# LED.net
KiCad netlist of a schematic drawn in Altium Designer
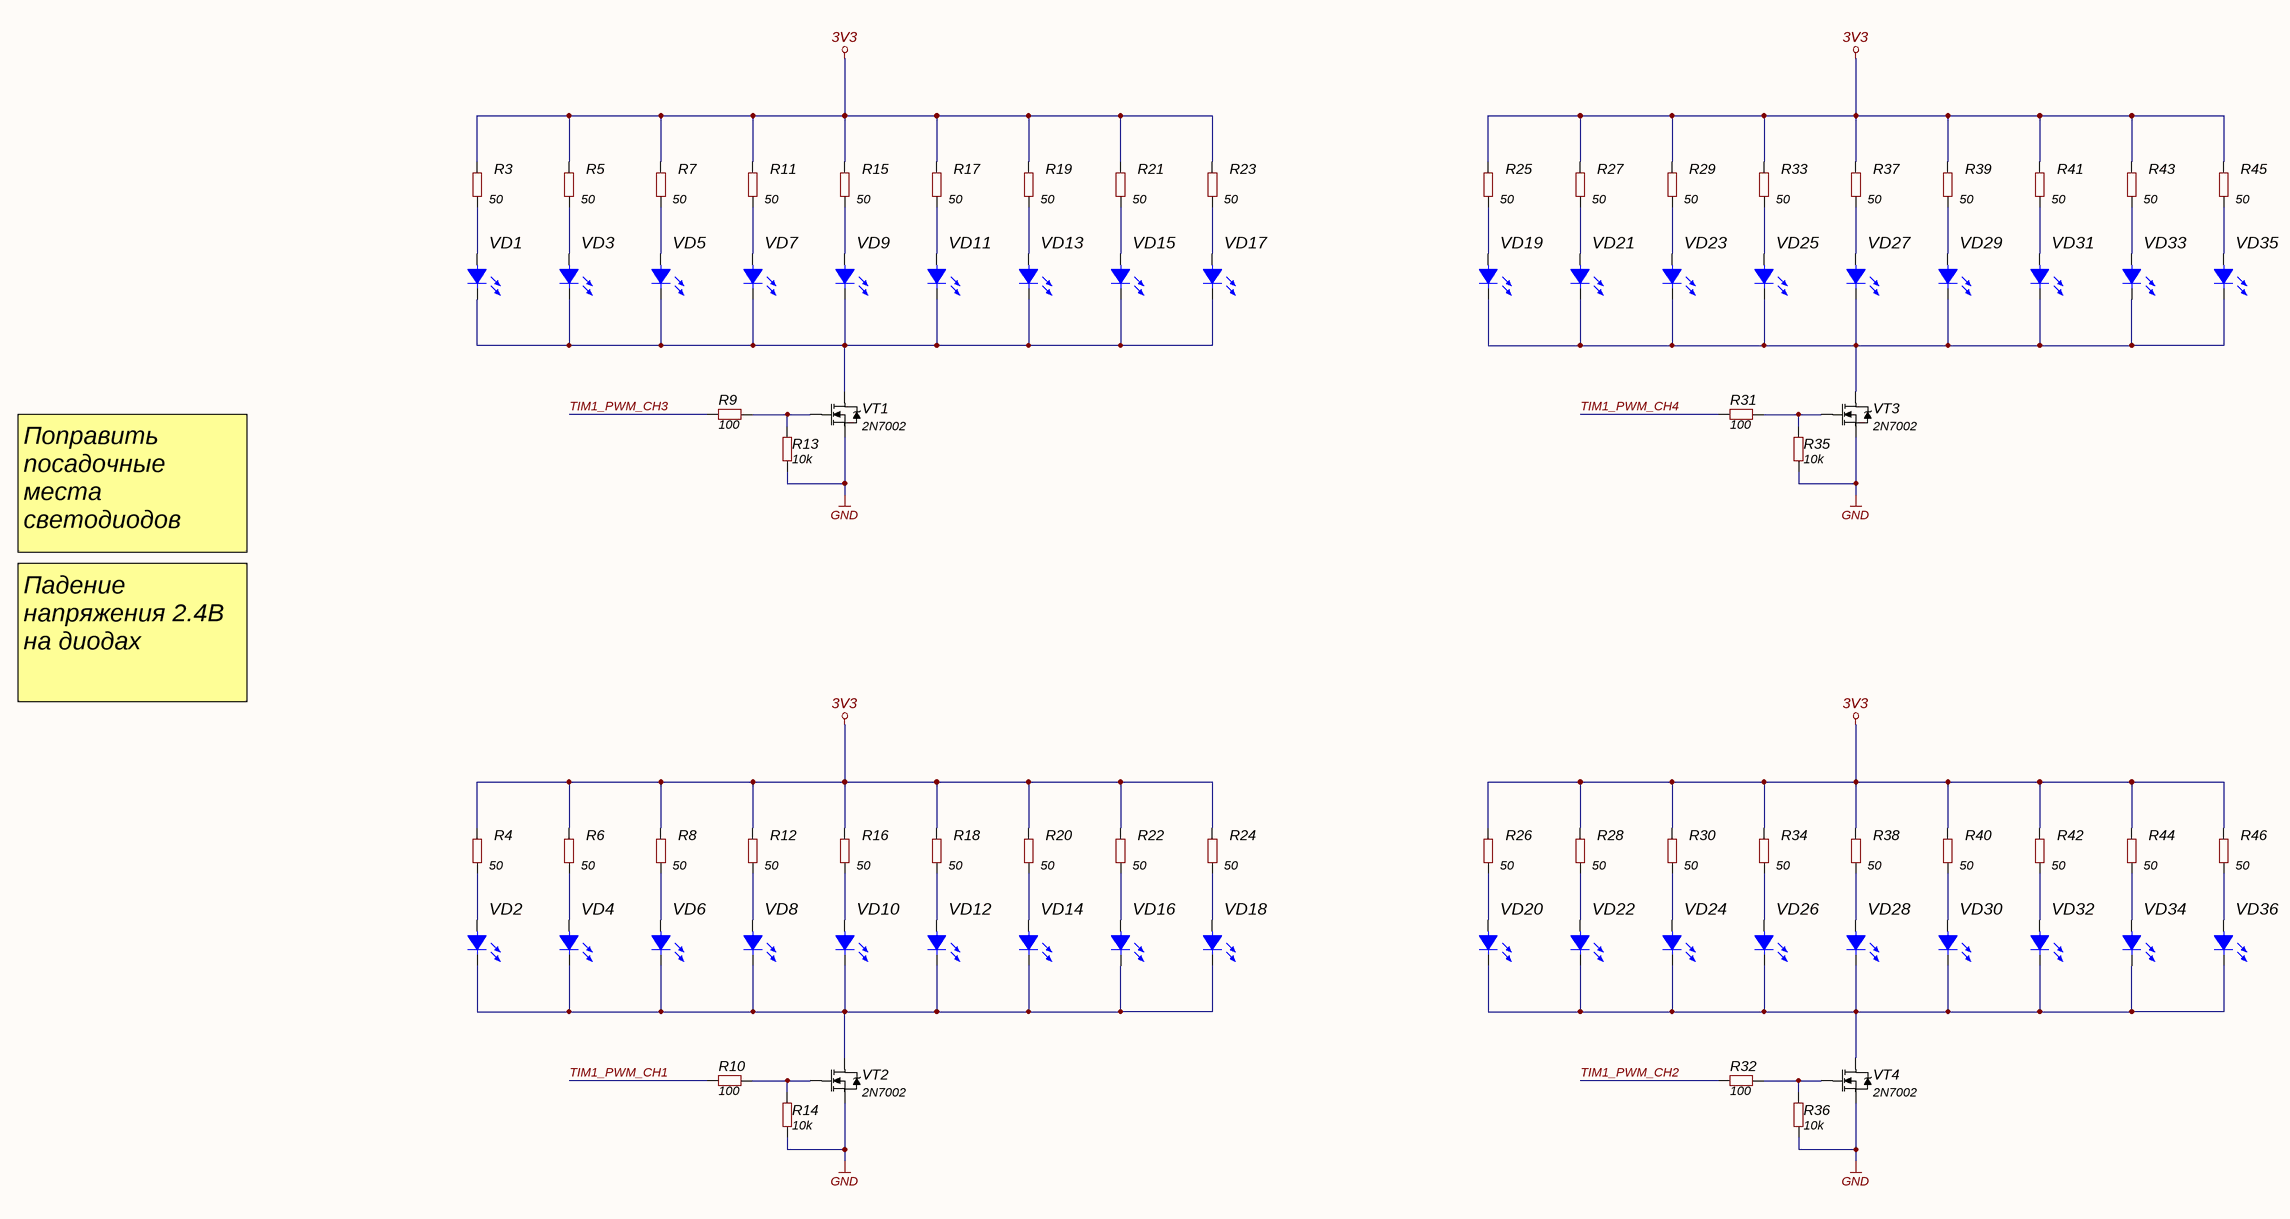
[diagram p0: LED.SchDoc]

(export (version "E")
  (design (tool "Eeschema 10.0.6"))
  (components
    (comp (ref "R3")
      (value "50")
      (footprint "RES: 0603")
      (fields
        (field (name "MANUFACTURER") "Yageo")
        (field (name "PARTNUMBER") "RC0603JR-07100RL")
        (field (name "VALUEMANUFACTURERPARTNUMBER") "Resistor film, 50, , 0603, 0.1W, -55...+125°C")
      )
      (libsource (lib "resistor") (part "Resistor_0603"))
    )
    (comp (ref "R4")
      (value "50")
      (footprint "RES: 0603")
      (fields
        (field (name "MANUFACTURER") "Yageo")
        (field (name "PARTNUMBER") "RC0603JR-07100RL")
        (field (name "VALUEMANUFACTURERPARTNUMBER") "Resistor film, 50, , 0603, 0.1W, -55...+125°C")
      )
      (libsource (lib "resistor") (part "Resistor_0603"))
    )
    (comp (ref "R5")
      (value "50")
      (footprint "RES: 0603")
      (fields
        (field (name "MANUFACTURER") "Yageo")
        (field (name "PARTNUMBER") "RC0603JR-07100RL")
        (field (name "VALUEMANUFACTURERPARTNUMBER") "Resistor film, 50, , 0603, 0.1W, -55...+125°C")
      )
      (libsource (lib "resistor") (part "Resistor_0603"))
    )
    (comp (ref "R6")
      (value "50")
      (footprint "RES: 0603")
      (fields
        (field (name "MANUFACTURER") "Yageo")
        (field (name "PARTNUMBER") "RC0603JR-07100RL")
        (field (name "VALUEMANUFACTURERPARTNUMBER") "Resistor film, 50, , 0603, 0.1W, -55...+125°C")
      )
      (libsource (lib "resistor") (part "Resistor_0603"))
    )
    (comp (ref "R7")
      (value "50")
      (footprint "RES: 0603")
      (fields
        (field (name "MANUFACTURER") "Yageo")
        (field (name "PARTNUMBER") "RC0603JR-07100RL")
        (field (name "VALUEMANUFACTURERPARTNUMBER") "Resistor film, 50, , 0603, 0.1W, -55...+125°C")
      )
      (libsource (lib "resistor") (part "Resistor_0603"))
    )
    (comp (ref "R8")
      (value "50")
      (footprint "RES: 0603")
      (fields
        (field (name "MANUFACTURER") "Yageo")
        (field (name "PARTNUMBER") "RC0603JR-07100RL")
        (field (name "VALUEMANUFACTURERPARTNUMBER") "Resistor film, 50, , 0603, 0.1W, -55...+125°C")
      )
      (libsource (lib "resistor") (part "Resistor_0603"))
    )
    (comp (ref "R9")
      (value "100")
      (footprint "RES: 0603")
      (fields
        (field (name "MANUFACTURER") "Yageo")
        (field (name "PARTNUMBER") "RC0603JR-07100RL")
        (field (name "VALUEMANUFACTURERPARTNUMBER") "Resistor film, 100, , 0603, 0.1W, -55...+125°C")
      )
      (libsource (lib "") (part "Resistor_0603_1"))
    )
    (comp (ref "R10")
      (value "100")
      (footprint "RES: 0603")
      (fields
        (field (name "MANUFACTURER") "Yageo")
        (field (name "PARTNUMBER") "RC0603JR-07100RL")
        (field (name "VALUEMANUFACTURERPARTNUMBER") "Resistor film, 100, , 0603, 0.1W, -55...+125°C")
      )
      (libsource (lib "") (part "Resistor_0603_1"))
    )
    (comp (ref "R11")
      (value "50")
      (footprint "RES: 0603")
      (fields
        (field (name "MANUFACTURER") "Yageo")
        (field (name "PARTNUMBER") "RC0603JR-07100RL")
        (field (name "VALUEMANUFACTURERPARTNUMBER") "Resistor film, 50, , 0603, 0.1W, -55...+125°C")
      )
      (libsource (lib "resistor") (part "Resistor_0603"))
    )
    (comp (ref "R12")
      (value "50")
      (footprint "RES: 0603")
      (fields
        (field (name "MANUFACTURER") "Yageo")
        (field (name "PARTNUMBER") "RC0603JR-07100RL")
        (field (name "VALUEMANUFACTURERPARTNUMBER") "Resistor film, 50, , 0603, 0.1W, -55...+125°C")
      )
      (libsource (lib "resistor") (part "Resistor_0603"))
    )
    (comp (ref "R13")
      (value "10k")
      (footprint "RES: 0603")
      (fields
        (field (name "MANUFACTURER") "Yageo")
        (field (name "PARTNUMBER") "RC0603JR-07100RL")
        (field (name "VALUEMANUFACTURERPARTNUMBER") "Resistor film, 10k, , 0603, 0.1W, -55...+125°C")
      )
      (libsource (lib "resistor") (part "Resistor_0603"))
    )
    (comp (ref "R14")
      (value "10k")
      (footprint "RES: 0603")
      (fields
        (field (name "MANUFACTURER") "Yageo")
        (field (name "PARTNUMBER") "RC0603JR-07100RL")
        (field (name "VALUEMANUFACTURERPARTNUMBER") "Resistor film, 10k, , 0603, 0.1W, -55...+125°C")
      )
      (libsource (lib "resistor") (part "Resistor_0603"))
    )
    (comp (ref "R15")
      (value "50")
      (footprint "RES: 0603")
      (fields
        (field (name "MANUFACTURER") "Yageo")
        (field (name "PARTNUMBER") "RC0603JR-07100RL")
        (field (name "VALUEMANUFACTURERPARTNUMBER") "Resistor film, 50, , 0603, 0.1W, -55...+125°C")
      )
      (libsource (lib "resistor") (part "Resistor_0603"))
    )
    (comp (ref "R16")
      (value "50")
      (footprint "RES: 0603")
      (fields
        (field (name "MANUFACTURER") "Yageo")
        (field (name "PARTNUMBER") "RC0603JR-07100RL")
        (field (name "VALUEMANUFACTURERPARTNUMBER") "Resistor film, 50, , 0603, 0.1W, -55...+125°C")
      )
      (libsource (lib "resistor") (part "Resistor_0603"))
    )
    (comp (ref "R17")
      (value "50")
      (footprint "RES: 0603")
      (fields
        (field (name "MANUFACTURER") "Yageo")
        (field (name "PARTNUMBER") "RC0603JR-07100RL")
        (field (name "VALUEMANUFACTURERPARTNUMBER") "Resistor film, 50, , 0603, 0.1W, -55...+125°C")
      )
      (libsource (lib "resistor") (part "Resistor_0603"))
    )
    (comp (ref "R18")
      (value "50")
      (footprint "RES: 0603")
      (fields
        (field (name "MANUFACTURER") "Yageo")
        (field (name "PARTNUMBER") "RC0603JR-07100RL")
        (field (name "VALUEMANUFACTURERPARTNUMBER") "Resistor film, 50, , 0603, 0.1W, -55...+125°C")
      )
      (libsource (lib "resistor") (part "Resistor_0603"))
    )
    (comp (ref "R19")
      (value "50")
      (footprint "RES: 0603")
      (fields
        (field (name "MANUFACTURER") "Yageo")
        (field (name "PARTNUMBER") "RC0603JR-07100RL")
        (field (name "VALUEMANUFACTURERPARTNUMBER") "Resistor film, 50, , 0603, 0.1W, -55...+125°C")
      )
      (libsource (lib "resistor") (part "Resistor_0603"))
    )
    (comp (ref "R20")
      (value "50")
      (footprint "RES: 0603")
      (fields
        (field (name "MANUFACTURER") "Yageo")
        (field (name "PARTNUMBER") "RC0603JR-07100RL")
        (field (name "VALUEMANUFACTURERPARTNUMBER") "Resistor film, 50, , 0603, 0.1W, -55...+125°C")
      )
      (libsource (lib "resistor") (part "Resistor_0603"))
    )
    (comp (ref "R21")
      (value "50")
      (footprint "RES: 0603")
      (fields
        (field (name "MANUFACTURER") "Yageo")
        (field (name "PARTNUMBER") "RC0603JR-07100RL")
        (field (name "VALUEMANUFACTURERPARTNUMBER") "Resistor film, 50, , 0603, 0.1W, -55...+125°C")
      )
      (libsource (lib "resistor") (part "Resistor_0603"))
    )
    (comp (ref "R22")
      (value "50")
      (footprint "RES: 0603")
      (fields
        (field (name "MANUFACTURER") "Yageo")
        (field (name "PARTNUMBER") "RC0603JR-07100RL")
        (field (name "VALUEMANUFACTURERPARTNUMBER") "Resistor film, 50, , 0603, 0.1W, -55...+125°C")
      )
      (libsource (lib "resistor") (part "Resistor_0603"))
    )
    (comp (ref "R23")
      (value "50")
      (footprint "RES: 0603")
      (fields
        (field (name "MANUFACTURER") "Yageo")
        (field (name "PARTNUMBER") "RC0603JR-07100RL")
        (field (name "VALUEMANUFACTURERPARTNUMBER") "Resistor film, 50, , 0603, 0.1W, -55...+125°C")
      )
      (libsource (lib "resistor") (part "Resistor_0603"))
    )
    (comp (ref "R24")
      (value "50")
      (footprint "RES: 0603")
      (fields
        (field (name "MANUFACTURER") "Yageo")
        (field (name "PARTNUMBER") "RC0603JR-07100RL")
        (field (name "VALUEMANUFACTURERPARTNUMBER") "Resistor film, 50, , 0603, 0.1W, -55...+125°C")
      )
      (libsource (lib "resistor") (part "Resistor_0603"))
    )
    (comp (ref "R25")
      (value "50")
      (footprint "RES: 0603")
      (fields
        (field (name "MANUFACTURER") "Yageo")
        (field (name "PARTNUMBER") "RC0603JR-07100RL")
        (field (name "VALUEMANUFACTURERPARTNUMBER") "Resistor film, 50, , 0603, 0.1W, -55...+125°C")
      )
      (libsource (lib "resistor") (part "Resistor_0603"))
    )
    (comp (ref "R26")
      (value "50")
      (footprint "RES: 0603")
      (fields
        (field (name "MANUFACTURER") "Yageo")
        (field (name "PARTNUMBER") "RC0603JR-07100RL")
        (field (name "VALUEMANUFACTURERPARTNUMBER") "Resistor film, 50, , 0603, 0.1W, -55...+125°C")
      )
      (libsource (lib "resistor") (part "Resistor_0603"))
    )
    (comp (ref "R27")
      (value "50")
      (footprint "RES: 0603")
      (fields
        (field (name "MANUFACTURER") "Yageo")
        (field (name "PARTNUMBER") "RC0603JR-07100RL")
        (field (name "VALUEMANUFACTURERPARTNUMBER") "Resistor film, 50, , 0603, 0.1W, -55...+125°C")
      )
      (libsource (lib "resistor") (part "Resistor_0603"))
    )
    (comp (ref "R28")
      (value "50")
      (footprint "RES: 0603")
      (fields
        (field (name "MANUFACTURER") "Yageo")
        (field (name "PARTNUMBER") "RC0603JR-07100RL")
        (field (name "VALUEMANUFACTURERPARTNUMBER") "Resistor film, 50, , 0603, 0.1W, -55...+125°C")
      )
      (libsource (lib "resistor") (part "Resistor_0603"))
    )
    (comp (ref "R29")
      (value "50")
      (footprint "RES: 0603")
      (fields
        (field (name "MANUFACTURER") "Yageo")
        (field (name "PARTNUMBER") "RC0603JR-07100RL")
        (field (name "VALUEMANUFACTURERPARTNUMBER") "Resistor film, 50, , 0603, 0.1W, -55...+125°C")
      )
      (libsource (lib "resistor") (part "Resistor_0603"))
    )
    (comp (ref "R30")
      (value "50")
      (footprint "RES: 0603")
      (fields
        (field (name "MANUFACTURER") "Yageo")
        (field (name "PARTNUMBER") "RC0603JR-07100RL")
        (field (name "VALUEMANUFACTURERPARTNUMBER") "Resistor film, 50, , 0603, 0.1W, -55...+125°C")
      )
      (libsource (lib "resistor") (part "Resistor_0603"))
    )
    (comp (ref "R31")
      (value "100")
      (footprint "RES: 0603")
      (fields
        (field (name "MANUFACTURER") "Yageo")
        (field (name "PARTNUMBER") "RC0603JR-07100RL")
        (field (name "VALUEMANUFACTURERPARTNUMBER") "Resistor film, 100, , 0603, 0.1W, -55...+125°C")
      )
      (libsource (lib "") (part "Resistor_0603_1"))
    )
    (comp (ref "R32")
      (value "100")
      (footprint "RES: 0603")
      (fields
        (field (name "MANUFACTURER") "Yageo")
        (field (name "PARTNUMBER") "RC0603JR-07100RL")
        (field (name "VALUEMANUFACTURERPARTNUMBER") "Resistor film, 100, , 0603, 0.1W, -55...+125°C")
      )
      (libsource (lib "") (part "Resistor_0603_1"))
    )
    (comp (ref "R33")
      (value "50")
      (footprint "RES: 0603")
      (fields
        (field (name "MANUFACTURER") "Yageo")
        (field (name "PARTNUMBER") "RC0603JR-07100RL")
        (field (name "VALUEMANUFACTURERPARTNUMBER") "Resistor film, 50, , 0603, 0.1W, -55...+125°C")
      )
      (libsource (lib "resistor") (part "Resistor_0603"))
    )
    (comp (ref "R34")
      (value "50")
      (footprint "RES: 0603")
      (fields
        (field (name "MANUFACTURER") "Yageo")
        (field (name "PARTNUMBER") "RC0603JR-07100RL")
        (field (name "VALUEMANUFACTURERPARTNUMBER") "Resistor film, 50, , 0603, 0.1W, -55...+125°C")
      )
      (libsource (lib "resistor") (part "Resistor_0603"))
    )
    (comp (ref "R35")
      (value "10k")
      (footprint "RES: 0603")
      (fields
        (field (name "MANUFACTURER") "Yageo")
        (field (name "PARTNUMBER") "RC0603JR-07100RL")
        (field (name "VALUEMANUFACTURERPARTNUMBER") "Resistor film, 10k, , 0603, 0.1W, -55...+125°C")
      )
      (libsource (lib "resistor") (part "Resistor_0603"))
    )
    (comp (ref "R36")
      (value "10k")
      (footprint "RES: 0603")
      (fields
        (field (name "MANUFACTURER") "Yageo")
        (field (name "PARTNUMBER") "RC0603JR-07100RL")
        (field (name "VALUEMANUFACTURERPARTNUMBER") "Resistor film, 10k, , 0603, 0.1W, -55...+125°C")
      )
      (libsource (lib "resistor") (part "Resistor_0603"))
    )
    (comp (ref "R37")
      (value "50")
      (footprint "RES: 0603")
      (fields
        (field (name "MANUFACTURER") "Yageo")
        (field (name "PARTNUMBER") "RC0603JR-07100RL")
        (field (name "VALUEMANUFACTURERPARTNUMBER") "Resistor film, 50, , 0603, 0.1W, -55...+125°C")
      )
      (libsource (lib "resistor") (part "Resistor_0603"))
    )
    (comp (ref "R38")
      (value "50")
      (footprint "RES: 0603")
      (fields
        (field (name "MANUFACTURER") "Yageo")
        (field (name "PARTNUMBER") "RC0603JR-07100RL")
        (field (name "VALUEMANUFACTURERPARTNUMBER") "Resistor film, 50, , 0603, 0.1W, -55...+125°C")
      )
      (libsource (lib "resistor") (part "Resistor_0603"))
    )
    (comp (ref "R39")
      (value "50")
      (footprint "RES: 0603")
      (fields
        (field (name "MANUFACTURER") "Yageo")
        (field (name "PARTNUMBER") "RC0603JR-07100RL")
        (field (name "VALUEMANUFACTURERPARTNUMBER") "Resistor film, 50, , 0603, 0.1W, -55...+125°C")
      )
      (libsource (lib "resistor") (part "Resistor_0603"))
    )
    (comp (ref "R40")
      (value "50")
      (footprint "RES: 0603")
      (fields
        (field (name "MANUFACTURER") "Yageo")
        (field (name "PARTNUMBER") "RC0603JR-07100RL")
        (field (name "VALUEMANUFACTURERPARTNUMBER") "Resistor film, 50, , 0603, 0.1W, -55...+125°C")
      )
      (libsource (lib "resistor") (part "Resistor_0603"))
    )
    (comp (ref "R41")
      (value "50")
      (footprint "RES: 0603")
      (fields
        (field (name "MANUFACTURER") "Yageo")
        (field (name "PARTNUMBER") "RC0603JR-07100RL")
        (field (name "VALUEMANUFACTURERPARTNUMBER") "Resistor film, 50, , 0603, 0.1W, -55...+125°C")
      )
      (libsource (lib "resistor") (part "Resistor_0603"))
    )
    (comp (ref "R42")
      (value "50")
      (footprint "RES: 0603")
      (fields
        (field (name "MANUFACTURER") "Yageo")
        (field (name "PARTNUMBER") "RC0603JR-07100RL")
        (field (name "VALUEMANUFACTURERPARTNUMBER") "Resistor film, 50, , 0603, 0.1W, -55...+125°C")
      )
      (libsource (lib "resistor") (part "Resistor_0603"))
    )
    (comp (ref "R43")
      (value "50")
      (footprint "RES: 0603")
      (fields
        (field (name "MANUFACTURER") "Yageo")
        (field (name "PARTNUMBER") "RC0603JR-07100RL")
        (field (name "VALUEMANUFACTURERPARTNUMBER") "Resistor film, 50, , 0603, 0.1W, -55...+125°C")
      )
      (libsource (lib "resistor") (part "Resistor_0603"))
    )
    (comp (ref "R44")
      (value "50")
      (footprint "RES: 0603")
      (fields
        (field (name "MANUFACTURER") "Yageo")
        (field (name "PARTNUMBER") "RC0603JR-07100RL")
        (field (name "VALUEMANUFACTURERPARTNUMBER") "Resistor film, 50, , 0603, 0.1W, -55...+125°C")
      )
      (libsource (lib "resistor") (part "Resistor_0603"))
    )
    (comp (ref "R45")
      (value "50")
      (footprint "RES: 0603")
      (fields
        (field (name "MANUFACTURER") "Yageo")
        (field (name "PARTNUMBER") "RC0603JR-07100RL")
        (field (name "VALUEMANUFACTURERPARTNUMBER") "Resistor film, 50, , 0603, 0.1W, -55...+125°C")
      )
      (libsource (lib "resistor") (part "Resistor_0603"))
    )
    (comp (ref "R46")
      (value "50")
      (footprint "RES: 0603")
      (fields
        (field (name "MANUFACTURER") "Yageo")
        (field (name "PARTNUMBER") "RC0603JR-07100RL")
        (field (name "VALUEMANUFACTURERPARTNUMBER") "Resistor film, 50, , 0603, 0.1W, -55...+125°C")
      )
      (libsource (lib "resistor") (part "Resistor_0603"))
    )
    (comp (ref "VD1")
      (value "~")
      (footprint "LED: 1206Y")
      (fields (field (name "VALUEMANUFACTURERPARTNUMBER") "LED, Green, *, *, *, -55...+150°C"))
      (libsource (lib "diode") (part "LED_single"))
    )
    (comp (ref "VD2")
      (value "~")
      (footprint "LED: 1206Y")
      (fields (field (name "VALUEMANUFACTURERPARTNUMBER") "LED, Green, *, *, *, -55...+150°C"))
      (libsource (lib "diode") (part "LED_single"))
    )
    (comp (ref "VD3")
      (value "~")
      (footprint "LED: 1206Y")
      (fields (field (name "VALUEMANUFACTURERPARTNUMBER") "LED, Green, *, *, *, -55...+150°C"))
      (libsource (lib "diode") (part "LED_single"))
    )
    (comp (ref "VD4")
      (value "~")
      (footprint "LED: 1206Y")
      (fields (field (name "VALUEMANUFACTURERPARTNUMBER") "LED, Green, *, *, *, -55...+150°C"))
      (libsource (lib "diode") (part "LED_single"))
    )
    (comp (ref "VD5")
      (value "~")
      (footprint "LED: 1206Y")
      (fields (field (name "VALUEMANUFACTURERPARTNUMBER") "LED, Green, *, *, *, -55...+150°C"))
      (libsource (lib "diode") (part "LED_single"))
    )
    (comp (ref "VD6")
      (value "~")
      (footprint "LED: 1206Y")
      (fields (field (name "VALUEMANUFACTURERPARTNUMBER") "LED, Green, *, *, *, -55...+150°C"))
      (libsource (lib "diode") (part "LED_single"))
    )
    (comp (ref "VD7")
      (value "~")
      (footprint "LED: 1206Y")
      (fields (field (name "VALUEMANUFACTURERPARTNUMBER") "LED, Green, *, *, *, -55...+150°C"))
      (libsource (lib "diode") (part "LED_single"))
    )
    (comp (ref "VD8")
      (value "~")
      (footprint "LED: 1206Y")
      (fields (field (name "VALUEMANUFACTURERPARTNUMBER") "LED, Green, *, *, *, -55...+150°C"))
      (libsource (lib "diode") (part "LED_single"))
    )
    (comp (ref "VD9")
      (value "~")
      (footprint "LED: 1206Y")
      (fields (field (name "VALUEMANUFACTURERPARTNUMBER") "LED, Green, *, *, *, -55...+150°C"))
      (libsource (lib "diode") (part "LED_single"))
    )
    (comp (ref "VD10")
      (value "~")
      (footprint "LED: 1206Y")
      (fields (field (name "VALUEMANUFACTURERPARTNUMBER") "LED, Green, *, *, *, -55...+150°C"))
      (libsource (lib "diode") (part "LED_single"))
    )
    (comp (ref "VD11")
      (value "~")
      (footprint "LED: 1206Y")
      (fields (field (name "VALUEMANUFACTURERPARTNUMBER") "LED, Green, *, *, *, -55...+150°C"))
      (libsource (lib "diode") (part "LED_single"))
    )
    (comp (ref "VD12")
      (value "~")
      (footprint "LED: 1206Y")
      (fields (field (name "VALUEMANUFACTURERPARTNUMBER") "LED, Green, *, *, *, -55...+150°C"))
      (libsource (lib "diode") (part "LED_single"))
    )
    (comp (ref "VD13")
      (value "~")
      (footprint "LED: 1206Y")
      (fields (field (name "VALUEMANUFACTURERPARTNUMBER") "LED, Green, *, *, *, -55...+150°C"))
      (libsource (lib "diode") (part "LED_single"))
    )
    (comp (ref "VD14")
      (value "~")
      (footprint "LED: 1206Y")
      (fields (field (name "VALUEMANUFACTURERPARTNUMBER") "LED, Green, *, *, *, -55...+150°C"))
      (libsource (lib "diode") (part "LED_single"))
    )
    (comp (ref "VD15")
      (value "~")
      (footprint "LED: 1206Y")
      (fields (field (name "VALUEMANUFACTURERPARTNUMBER") "LED, Green, *, *, *, -55...+150°C"))
      (libsource (lib "diode") (part "LED_single"))
    )
    (comp (ref "VD16")
      (value "~")
      (footprint "LED: 1206Y")
      (fields (field (name "VALUEMANUFACTURERPARTNUMBER") "LED, Green, *, *, *, -55...+150°C"))
      (libsource (lib "diode") (part "LED_single"))
    )
    (comp (ref "VD17")
      (value "~")
      (footprint "LED: 1206Y")
      (fields (field (name "VALUEMANUFACTURERPARTNUMBER") "LED, Green, *, *, *, -55...+150°C"))
      (libsource (lib "diode") (part "LED_single"))
    )
    (comp (ref "VD18")
      (value "~")
      (footprint "LED: 1206Y")
      (fields (field (name "VALUEMANUFACTURERPARTNUMBER") "LED, Green, *, *, *, -55...+150°C"))
      (libsource (lib "diode") (part "LED_single"))
    )
    (comp (ref "VD19")
      (value "~")
      (footprint "LED: 1206Y")
      (fields (field (name "VALUEMANUFACTURERPARTNUMBER") "LED, Green, *, *, *, -55...+150°C"))
      (libsource (lib "diode") (part "LED_single"))
    )
    (comp (ref "VD20")
      (value "~")
      (footprint "LED: 1206Y")
      (fields (field (name "VALUEMANUFACTURERPARTNUMBER") "LED, Green, *, *, *, -55...+150°C"))
      (libsource (lib "diode") (part "LED_single"))
    )
    (comp (ref "VD21")
      (value "~")
      (footprint "LED: 1206Y")
      (fields (field (name "VALUEMANUFACTURERPARTNUMBER") "LED, Green, *, *, *, -55...+150°C"))
      (libsource (lib "diode") (part "LED_single"))
    )
    (comp (ref "VD22")
      (value "~")
      (footprint "LED: 1206Y")
      (fields (field (name "VALUEMANUFACTURERPARTNUMBER") "LED, Green, *, *, *, -55...+150°C"))
      (libsource (lib "diode") (part "LED_single"))
    )
    (comp (ref "VD23")
      (value "~")
      (footprint "LED: 1206Y")
      (fields (field (name "VALUEMANUFACTURERPARTNUMBER") "LED, Green, *, *, *, -55...+150°C"))
      (libsource (lib "diode") (part "LED_single"))
    )
    (comp (ref "VD24")
      (value "~")
      (footprint "LED: 1206Y")
      (fields (field (name "VALUEMANUFACTURERPARTNUMBER") "LED, Green, *, *, *, -55...+150°C"))
      (libsource (lib "diode") (part "LED_single"))
    )
    (comp (ref "VD25")
      (value "~")
      (footprint "LED: 1206Y")
      (fields (field (name "VALUEMANUFACTURERPARTNUMBER") "LED, Green, *, *, *, -55...+150°C"))
      (libsource (lib "diode") (part "LED_single"))
    )
    (comp (ref "VD26")
      (value "~")
      (footprint "LED: 1206Y")
      (fields (field (name "VALUEMANUFACTURERPARTNUMBER") "LED, Green, *, *, *, -55...+150°C"))
      (libsource (lib "diode") (part "LED_single"))
    )
    (comp (ref "VD27")
      (value "~")
      (footprint "LED: 1206Y")
      (fields (field (name "VALUEMANUFACTURERPARTNUMBER") "LED, Green, *, *, *, -55...+150°C"))
      (libsource (lib "diode") (part "LED_single"))
    )
    (comp (ref "VD28")
      (value "~")
      (footprint "LED: 1206Y")
      (fields (field (name "VALUEMANUFACTURERPARTNUMBER") "LED, Green, *, *, *, -55...+150°C"))
      (libsource (lib "diode") (part "LED_single"))
    )
    (comp (ref "VD29")
      (value "~")
      (footprint "LED: 1206Y")
      (fields (field (name "VALUEMANUFACTURERPARTNUMBER") "LED, Green, *, *, *, -55...+150°C"))
      (libsource (lib "diode") (part "LED_single"))
    )
    (comp (ref "VD30")
      (value "~")
      (footprint "LED: 1206Y")
      (fields (field (name "VALUEMANUFACTURERPARTNUMBER") "LED, Green, *, *, *, -55...+150°C"))
      (libsource (lib "diode") (part "LED_single"))
    )
    (comp (ref "VD31")
      (value "~")
      (footprint "LED: 1206Y")
      (fields (field (name "VALUEMANUFACTURERPARTNUMBER") "LED, Green, *, *, *, -55...+150°C"))
      (libsource (lib "diode") (part "LED_single"))
    )
    (comp (ref "VD32")
      (value "~")
      (footprint "LED: 1206Y")
      (fields (field (name "VALUEMANUFACTURERPARTNUMBER") "LED, Green, *, *, *, -55...+150°C"))
      (libsource (lib "diode") (part "LED_single"))
    )
    (comp (ref "VD33")
      (value "~")
      (footprint "LED: 1206Y")
      (fields (field (name "VALUEMANUFACTURERPARTNUMBER") "LED, Green, *, *, *, -55...+150°C"))
      (libsource (lib "diode") (part "LED_single"))
    )
    (comp (ref "VD34")
      (value "~")
      (footprint "LED: 1206Y")
      (fields (field (name "VALUEMANUFACTURERPARTNUMBER") "LED, Green, *, *, *, -55...+150°C"))
      (libsource (lib "diode") (part "LED_single"))
    )
    (comp (ref "VD35")
      (value "~")
      (footprint "LED: 1206Y")
      (fields (field (name "VALUEMANUFACTURERPARTNUMBER") "LED, Green, *, *, *, -55...+150°C"))
      (libsource (lib "diode") (part "LED_single"))
    )
    (comp (ref "VD36")
      (value "~")
      (footprint "LED: 1206Y")
      (fields (field (name "VALUEMANUFACTURERPARTNUMBER") "LED, Green, *, *, *, -55...+150°C"))
      (libsource (lib "diode") (part "LED_single"))
    )
    (comp (ref "VT1")
      (value "~")
      (footprint "SOT23")
      (fields
        (field (name "MANUFACTURER") "Infineon Technologies")
        (field (name "VALUEMANUFACTURERPARTNUMBER") "MOSFET N-channel transistor, 80V, 7A, 9.1nC, 2.5W, 34mOhm, 756pF, 8-TDSON, -55...+150°C")
        (field (name "PARTNUMBER") "2N7002")
      )
      (libsource (lib "transistor") (part "MOSFET_N_132"))
    )
    (comp (ref "VT2")
      (value "~")
      (footprint "SOT23")
      (fields
        (field (name "MANUFACTURER") "Infineon Technologies")
        (field (name "VALUEMANUFACTURERPARTNUMBER") "MOSFET N-channel transistor, 80V, 7A, 9.1nC, 2.5W, 34mOhm, 756pF, 8-TDSON, -55...+150°C")
        (field (name "PARTNUMBER") "2N7002")
      )
      (libsource (lib "transistor") (part "MOSFET_N_132"))
    )
    (comp (ref "VT3")
      (value "~")
      (footprint "SOT23")
      (fields
        (field (name "MANUFACTURER") "Infineon Technologies")
        (field (name "VALUEMANUFACTURERPARTNUMBER") "MOSFET N-channel transistor, 80V, 7A, 9.1nC, 2.5W, 34mOhm, 756pF, 8-TDSON, -55...+150°C")
        (field (name "PARTNUMBER") "2N7002")
      )
      (libsource (lib "transistor") (part "MOSFET_N_132"))
    )
    (comp (ref "VT4")
      (value "~")
      (footprint "SOT23")
      (fields
        (field (name "MANUFACTURER") "Infineon Technologies")
        (field (name "VALUEMANUFACTURERPARTNUMBER") "MOSFET N-channel transistor, 80V, 7A, 9.1nC, 2.5W, 34mOhm, 756pF, 8-TDSON, -55...+150°C")
        (field (name "PARTNUMBER") "2N7002")
      )
      (libsource (lib "transistor") (part "MOSFET_N_132"))
    )
  )
  (nets
    (net (code "1") (name "/TIM1_PWM_CH1") (class "Default")
      (node (ref "R10") (pin "1") (pinfunction "1_1") (pintype "passive"))
    )
    (net (code "2") (name "/TIM1_PWM_CH2") (class "Default")
      (node (ref "R32") (pin "1") (pinfunction "1_1") (pintype "passive"))
    )
    (net (code "3") (name "/TIM1_PWM_CH3") (class "Default")
      (node (ref "R9") (pin "1") (pinfunction "1_1") (pintype "passive"))
    )
    (net (code "4") (name "/TIM1_PWM_CH4") (class "Default")
      (node (ref "R31") (pin "1") (pinfunction "1_1") (pintype "passive"))
    )
    (net (code "5") (name "3V3") (class "Default")
      (node (ref "R11") (pin "2") (pinfunction "2_2") (pintype "passive"))
      (node (ref "R12") (pin "2") (pinfunction "2_2") (pintype "passive"))
      (node (ref "R15") (pin "2") (pinfunction "2_2") (pintype "passive"))
      (node (ref "R16") (pin "2") (pinfunction "2_2") (pintype "passive"))
      (node (ref "R17") (pin "2") (pinfunction "2_2") (pintype "passive"))
      (node (ref "R18") (pin "2") (pinfunction "2_2") (pintype "passive"))
      (node (ref "R19") (pin "2") (pinfunction "2_2") (pintype "passive"))
      (node (ref "R20") (pin "2") (pinfunction "2_2") (pintype "passive"))
      (node (ref "R21") (pin "2") (pinfunction "2_2") (pintype "passive"))
      (node (ref "R22") (pin "2") (pinfunction "2_2") (pintype "passive"))
      (node (ref "R23") (pin "2") (pinfunction "2_2") (pintype "passive"))
      (node (ref "R24") (pin "2") (pinfunction "2_2") (pintype "passive"))
      (node (ref "R25") (pin "2") (pinfunction "2_2") (pintype "passive"))
      (node (ref "R26") (pin "2") (pinfunction "2_2") (pintype "passive"))
      (node (ref "R27") (pin "2") (pinfunction "2_2") (pintype "passive"))
      (node (ref "R28") (pin "2") (pinfunction "2_2") (pintype "passive"))
      (node (ref "R29") (pin "2") (pinfunction "2_2") (pintype "passive"))
      (node (ref "R3") (pin "2") (pinfunction "2_2") (pintype "passive"))
      (node (ref "R30") (pin "2") (pinfunction "2_2") (pintype "passive"))
      (node (ref "R33") (pin "2") (pinfunction "2_2") (pintype "passive"))
      (node (ref "R34") (pin "2") (pinfunction "2_2") (pintype "passive"))
      (node (ref "R37") (pin "2") (pinfunction "2_2") (pintype "passive"))
      (node (ref "R38") (pin "2") (pinfunction "2_2") (pintype "passive"))
      (node (ref "R39") (pin "2") (pinfunction "2_2") (pintype "passive"))
      (node (ref "R4") (pin "2") (pinfunction "2_2") (pintype "passive"))
      (node (ref "R40") (pin "2") (pinfunction "2_2") (pintype "passive"))
      (node (ref "R41") (pin "2") (pinfunction "2_2") (pintype "passive"))
      (node (ref "R42") (pin "2") (pinfunction "2_2") (pintype "passive"))
      (node (ref "R43") (pin "2") (pinfunction "2_2") (pintype "passive"))
      (node (ref "R44") (pin "2") (pinfunction "2_2") (pintype "passive"))
      (node (ref "R45") (pin "2") (pinfunction "2_2") (pintype "passive"))
      (node (ref "R46") (pin "2") (pinfunction "2_2") (pintype "passive"))
      (node (ref "R5") (pin "2") (pinfunction "2_2") (pintype "passive"))
      (node (ref "R6") (pin "2") (pinfunction "2_2") (pintype "passive"))
      (node (ref "R7") (pin "2") (pinfunction "2_2") (pintype "passive"))
      (node (ref "R8") (pin "2") (pinfunction "2_2") (pintype "passive"))
    )
    (net (code "6") (name "GND") (class "Default")
      (node (ref "R13") (pin "1") (pinfunction "1_1") (pintype "passive"))
      (node (ref "R14") (pin "1") (pinfunction "1_1") (pintype "passive"))
      (node (ref "R35") (pin "1") (pinfunction "1_1") (pintype "passive"))
      (node (ref "R36") (pin "1") (pinfunction "1_1") (pintype "passive"))
      (node (ref "VT1") (pin "2") (pinfunction "S_2") (pintype "passive"))
      (node (ref "VT2") (pin "2") (pinfunction "S_2") (pintype "passive"))
      (node (ref "VT3") (pin "2") (pinfunction "S_2") (pintype "passive"))
      (node (ref "VT4") (pin "2") (pinfunction "S_2") (pintype "passive"))
    )
    (net (code "7") (name "Net-(VD1-A)") (class "Default")
      (node (ref "R3") (pin "1") (pinfunction "1_1") (pintype "passive"))
      (node (ref "VD1") (pin "1") (pinfunction "A_1") (pintype "passive"))
    )
    (net (code "8") (name "Net-(VD1-C)") (class "Default")
      (node (ref "VD1") (pin "2") (pinfunction "C_2") (pintype "passive"))
      (node (ref "VD11") (pin "2") (pinfunction "C_2") (pintype "passive"))
      (node (ref "VD13") (pin "2") (pinfunction "C_2") (pintype "passive"))
      (node (ref "VD15") (pin "2") (pinfunction "C_2") (pintype "passive"))
      (node (ref "VD17") (pin "2") (pinfunction "C_2") (pintype "passive"))
      (node (ref "VD3") (pin "2") (pinfunction "C_2") (pintype "passive"))
      (node (ref "VD5") (pin "2") (pinfunction "C_2") (pintype "passive"))
      (node (ref "VD7") (pin "2") (pinfunction "C_2") (pintype "passive"))
      (node (ref "VD9") (pin "2") (pinfunction "C_2") (pintype "passive"))
      (node (ref "VT1") (pin "3") (pinfunction "D_3") (pintype "passive"))
    )
    (net (code "9") (name "Net-(VD2-A)") (class "Default")
      (node (ref "R4") (pin "1") (pinfunction "1_1") (pintype "passive"))
      (node (ref "VD2") (pin "1") (pinfunction "A_1") (pintype "passive"))
    )
    (net (code "10") (name "Net-(VD3-A)") (class "Default")
      (node (ref "R5") (pin "1") (pinfunction "1_1") (pintype "passive"))
      (node (ref "VD3") (pin "1") (pinfunction "A_1") (pintype "passive"))
    )
    (net (code "11") (name "Net-(VD4-A)") (class "Default")
      (node (ref "R6") (pin "1") (pinfunction "1_1") (pintype "passive"))
      (node (ref "VD4") (pin "1") (pinfunction "A_1") (pintype "passive"))
    )
    (net (code "12") (name "Net-(VD5-A)") (class "Default")
      (node (ref "R7") (pin "1") (pinfunction "1_1") (pintype "passive"))
      (node (ref "VD5") (pin "1") (pinfunction "A_1") (pintype "passive"))
    )
    (net (code "13") (name "Net-(VD6-A)") (class "Default")
      (node (ref "R8") (pin "1") (pinfunction "1_1") (pintype "passive"))
      (node (ref "VD6") (pin "1") (pinfunction "A_1") (pintype "passive"))
    )
    (net (code "14") (name "Net-(VD7-A)") (class "Default")
      (node (ref "R11") (pin "1") (pinfunction "1_1") (pintype "passive"))
      (node (ref "VD7") (pin "1") (pinfunction "A_1") (pintype "passive"))
    )
    (net (code "15") (name "Net-(VD8-A)") (class "Default")
      (node (ref "R12") (pin "1") (pinfunction "1_1") (pintype "passive"))
      (node (ref "VD8") (pin "1") (pinfunction "A_1") (pintype "passive"))
    )
    (net (code "16") (name "Net-(VD9-A)") (class "Default")
      (node (ref "R15") (pin "1") (pinfunction "1_1") (pintype "passive"))
      (node (ref "VD9") (pin "1") (pinfunction "A_1") (pintype "passive"))
    )
    (net (code "17") (name "Net-(VD10-A)") (class "Default")
      (node (ref "R16") (pin "1") (pinfunction "1_1") (pintype "passive"))
      (node (ref "VD10") (pin "1") (pinfunction "A_1") (pintype "passive"))
    )
    (net (code "18") (name "Net-(VD10-C)") (class "Default")
      (node (ref "VD10") (pin "2") (pinfunction "C_2") (pintype "passive"))
      (node (ref "VD12") (pin "2") (pinfunction "C_2") (pintype "passive"))
      (node (ref "VD14") (pin "2") (pinfunction "C_2") (pintype "passive"))
      (node (ref "VD16") (pin "2") (pinfunction "C_2") (pintype "passive"))
      (node (ref "VD18") (pin "2") (pinfunction "C_2") (pintype "passive"))
      (node (ref "VD2") (pin "2") (pinfunction "C_2") (pintype "passive"))
      (node (ref "VD4") (pin "2") (pinfunction "C_2") (pintype "passive"))
      (node (ref "VD6") (pin "2") (pinfunction "C_2") (pintype "passive"))
      (node (ref "VD8") (pin "2") (pinfunction "C_2") (pintype "passive"))
      (node (ref "VT2") (pin "3") (pinfunction "D_3") (pintype "passive"))
    )
    (net (code "19") (name "Net-(VD11-A)") (class "Default")
      (node (ref "R17") (pin "1") (pinfunction "1_1") (pintype "passive"))
      (node (ref "VD11") (pin "1") (pinfunction "A_1") (pintype "passive"))
    )
    (net (code "20") (name "Net-(VD12-A)") (class "Default")
      (node (ref "R18") (pin "1") (pinfunction "1_1") (pintype "passive"))
      (node (ref "VD12") (pin "1") (pinfunction "A_1") (pintype "passive"))
    )
    (net (code "21") (name "Net-(VD13-A)") (class "Default")
      (node (ref "R19") (pin "1") (pinfunction "1_1") (pintype "passive"))
      (node (ref "VD13") (pin "1") (pinfunction "A_1") (pintype "passive"))
    )
    (net (code "22") (name "Net-(VD14-A)") (class "Default")
      (node (ref "R20") (pin "1") (pinfunction "1_1") (pintype "passive"))
      (node (ref "VD14") (pin "1") (pinfunction "A_1") (pintype "passive"))
    )
    (net (code "23") (name "Net-(VD15-A)") (class "Default")
      (node (ref "R21") (pin "1") (pinfunction "1_1") (pintype "passive"))
      (node (ref "VD15") (pin "1") (pinfunction "A_1") (pintype "passive"))
    )
    (net (code "24") (name "Net-(VD16-A)") (class "Default")
      (node (ref "R22") (pin "1") (pinfunction "1_1") (pintype "passive"))
      (node (ref "VD16") (pin "1") (pinfunction "A_1") (pintype "passive"))
    )
    (net (code "25") (name "Net-(VD17-A)") (class "Default")
      (node (ref "R23") (pin "1") (pinfunction "1_1") (pintype "passive"))
      (node (ref "VD17") (pin "1") (pinfunction "A_1") (pintype "passive"))
    )
    (net (code "26") (name "Net-(VD18-A)") (class "Default")
      (node (ref "R24") (pin "1") (pinfunction "1_1") (pintype "passive"))
      (node (ref "VD18") (pin "1") (pinfunction "A_1") (pintype "passive"))
    )
    (net (code "27") (name "Net-(VD19-A)") (class "Default")
      (node (ref "R25") (pin "1") (pinfunction "1_1") (pintype "passive"))
      (node (ref "VD19") (pin "1") (pinfunction "A_1") (pintype "passive"))
    )
    (net (code "28") (name "Net-(VD19-C)") (class "Default")
      (node (ref "VD19") (pin "2") (pinfunction "C_2") (pintype "passive"))
      (node (ref "VD21") (pin "2") (pinfunction "C_2") (pintype "passive"))
      (node (ref "VD23") (pin "2") (pinfunction "C_2") (pintype "passive"))
      (node (ref "VD25") (pin "2") (pinfunction "C_2") (pintype "passive"))
      (node (ref "VD27") (pin "2") (pinfunction "C_2") (pintype "passive"))
      (node (ref "VD29") (pin "2") (pinfunction "C_2") (pintype "passive"))
      (node (ref "VD31") (pin "2") (pinfunction "C_2") (pintype "passive"))
      (node (ref "VD33") (pin "2") (pinfunction "C_2") (pintype "passive"))
      (node (ref "VD35") (pin "2") (pinfunction "C_2") (pintype "passive"))
      (node (ref "VT3") (pin "3") (pinfunction "D_3") (pintype "passive"))
    )
    (net (code "29") (name "Net-(VD20-A)") (class "Default")
      (node (ref "R26") (pin "1") (pinfunction "1_1") (pintype "passive"))
      (node (ref "VD20") (pin "1") (pinfunction "A_1") (pintype "passive"))
    )
    (net (code "30") (name "Net-(VD20-C)") (class "Default")
      (node (ref "VD20") (pin "2") (pinfunction "C_2") (pintype "passive"))
      (node (ref "VD22") (pin "2") (pinfunction "C_2") (pintype "passive"))
      (node (ref "VD24") (pin "2") (pinfunction "C_2") (pintype "passive"))
      (node (ref "VD26") (pin "2") (pinfunction "C_2") (pintype "passive"))
      (node (ref "VD28") (pin "2") (pinfunction "C_2") (pintype "passive"))
      (node (ref "VD30") (pin "2") (pinfunction "C_2") (pintype "passive"))
      (node (ref "VD32") (pin "2") (pinfunction "C_2") (pintype "passive"))
      (node (ref "VD34") (pin "2") (pinfunction "C_2") (pintype "passive"))
      (node (ref "VD36") (pin "2") (pinfunction "C_2") (pintype "passive"))
      (node (ref "VT4") (pin "3") (pinfunction "D_3") (pintype "passive"))
    )
    (net (code "31") (name "Net-(VD21-A)") (class "Default")
      (node (ref "R27") (pin "1") (pinfunction "1_1") (pintype "passive"))
      (node (ref "VD21") (pin "1") (pinfunction "A_1") (pintype "passive"))
    )
    (net (code "32") (name "Net-(VD22-A)") (class "Default")
      (node (ref "R28") (pin "1") (pinfunction "1_1") (pintype "passive"))
      (node (ref "VD22") (pin "1") (pinfunction "A_1") (pintype "passive"))
    )
    (net (code "33") (name "Net-(VD23-A)") (class "Default")
      (node (ref "R29") (pin "1") (pinfunction "1_1") (pintype "passive"))
      (node (ref "VD23") (pin "1") (pinfunction "A_1") (pintype "passive"))
    )
    (net (code "34") (name "Net-(VD24-A)") (class "Default")
      (node (ref "R30") (pin "1") (pinfunction "1_1") (pintype "passive"))
      (node (ref "VD24") (pin "1") (pinfunction "A_1") (pintype "passive"))
    )
    (net (code "35") (name "Net-(VD25-A)") (class "Default")
      (node (ref "R33") (pin "1") (pinfunction "1_1") (pintype "passive"))
      (node (ref "VD25") (pin "1") (pinfunction "A_1") (pintype "passive"))
    )
    (net (code "36") (name "Net-(VD26-A)") (class "Default")
      (node (ref "R34") (pin "1") (pinfunction "1_1") (pintype "passive"))
      (node (ref "VD26") (pin "1") (pinfunction "A_1") (pintype "passive"))
    )
    (net (code "37") (name "Net-(VD27-A)") (class "Default")
      (node (ref "R37") (pin "1") (pinfunction "1_1") (pintype "passive"))
      (node (ref "VD27") (pin "1") (pinfunction "A_1") (pintype "passive"))
    )
    (net (code "38") (name "Net-(VD28-A)") (class "Default")
      (node (ref "R38") (pin "1") (pinfunction "1_1") (pintype "passive"))
      (node (ref "VD28") (pin "1") (pinfunction "A_1") (pintype "passive"))
    )
    (net (code "39") (name "Net-(VD29-A)") (class "Default")
      (node (ref "R39") (pin "1") (pinfunction "1_1") (pintype "passive"))
      (node (ref "VD29") (pin "1") (pinfunction "A_1") (pintype "passive"))
    )
    (net (code "40") (name "Net-(VD30-A)") (class "Default")
      (node (ref "R40") (pin "1") (pinfunction "1_1") (pintype "passive"))
      (node (ref "VD30") (pin "1") (pinfunction "A_1") (pintype "passive"))
    )
    (net (code "41") (name "Net-(VD31-A)") (class "Default")
      (node (ref "R41") (pin "1") (pinfunction "1_1") (pintype "passive"))
      (node (ref "VD31") (pin "1") (pinfunction "A_1") (pintype "passive"))
    )
    (net (code "42") (name "Net-(VD32-A)") (class "Default")
      (node (ref "R42") (pin "1") (pinfunction "1_1") (pintype "passive"))
      (node (ref "VD32") (pin "1") (pinfunction "A_1") (pintype "passive"))
    )
    (net (code "43") (name "Net-(VD33-A)") (class "Default")
      (node (ref "R43") (pin "1") (pinfunction "1_1") (pintype "passive"))
      (node (ref "VD33") (pin "1") (pinfunction "A_1") (pintype "passive"))
    )
    (net (code "44") (name "Net-(VD34-A)") (class "Default")
      (node (ref "R44") (pin "1") (pinfunction "1_1") (pintype "passive"))
      (node (ref "VD34") (pin "1") (pinfunction "A_1") (pintype "passive"))
    )
    (net (code "45") (name "Net-(VD35-A)") (class "Default")
      (node (ref "R45") (pin "1") (pinfunction "1_1") (pintype "passive"))
      (node (ref "VD35") (pin "1") (pinfunction "A_1") (pintype "passive"))
    )
    (net (code "46") (name "Net-(VD36-A)") (class "Default")
      (node (ref "R46") (pin "1") (pinfunction "1_1") (pintype "passive"))
      (node (ref "VD36") (pin "1") (pinfunction "A_1") (pintype "passive"))
    )
    (net (code "47") (name "Net-(VT1-G)") (class "Default")
      (node (ref "R13") (pin "2") (pinfunction "2_2") (pintype "passive"))
      (node (ref "R9") (pin "2") (pinfunction "2_2") (pintype "passive"))
      (node (ref "VT1") (pin "1") (pinfunction "G_1") (pintype "passive"))
    )
    (net (code "48") (name "Net-(VT2-G)") (class "Default")
      (node (ref "R10") (pin "2") (pinfunction "2_2") (pintype "passive"))
      (node (ref "R14") (pin "2") (pinfunction "2_2") (pintype "passive"))
      (node (ref "VT2") (pin "1") (pinfunction "G_1") (pintype "passive"))
    )
    (net (code "49") (name "Net-(VT3-G)") (class "Default")
      (node (ref "R31") (pin "2") (pinfunction "2_2") (pintype "passive"))
      (node (ref "R35") (pin "2") (pinfunction "2_2") (pintype "passive"))
      (node (ref "VT3") (pin "1") (pinfunction "G_1") (pintype "passive"))
    )
    (net (code "50") (name "Net-(VT4-G)") (class "Default")
      (node (ref "R32") (pin "2") (pinfunction "2_2") (pintype "passive"))
      (node (ref "R36") (pin "2") (pinfunction "2_2") (pintype "passive"))
      (node (ref "VT4") (pin "1") (pinfunction "G_1") (pintype "passive"))
    )
  )
)
